# nlp_base_0_2.net
KiCad netlist of a schematic drawn in EasyEDA
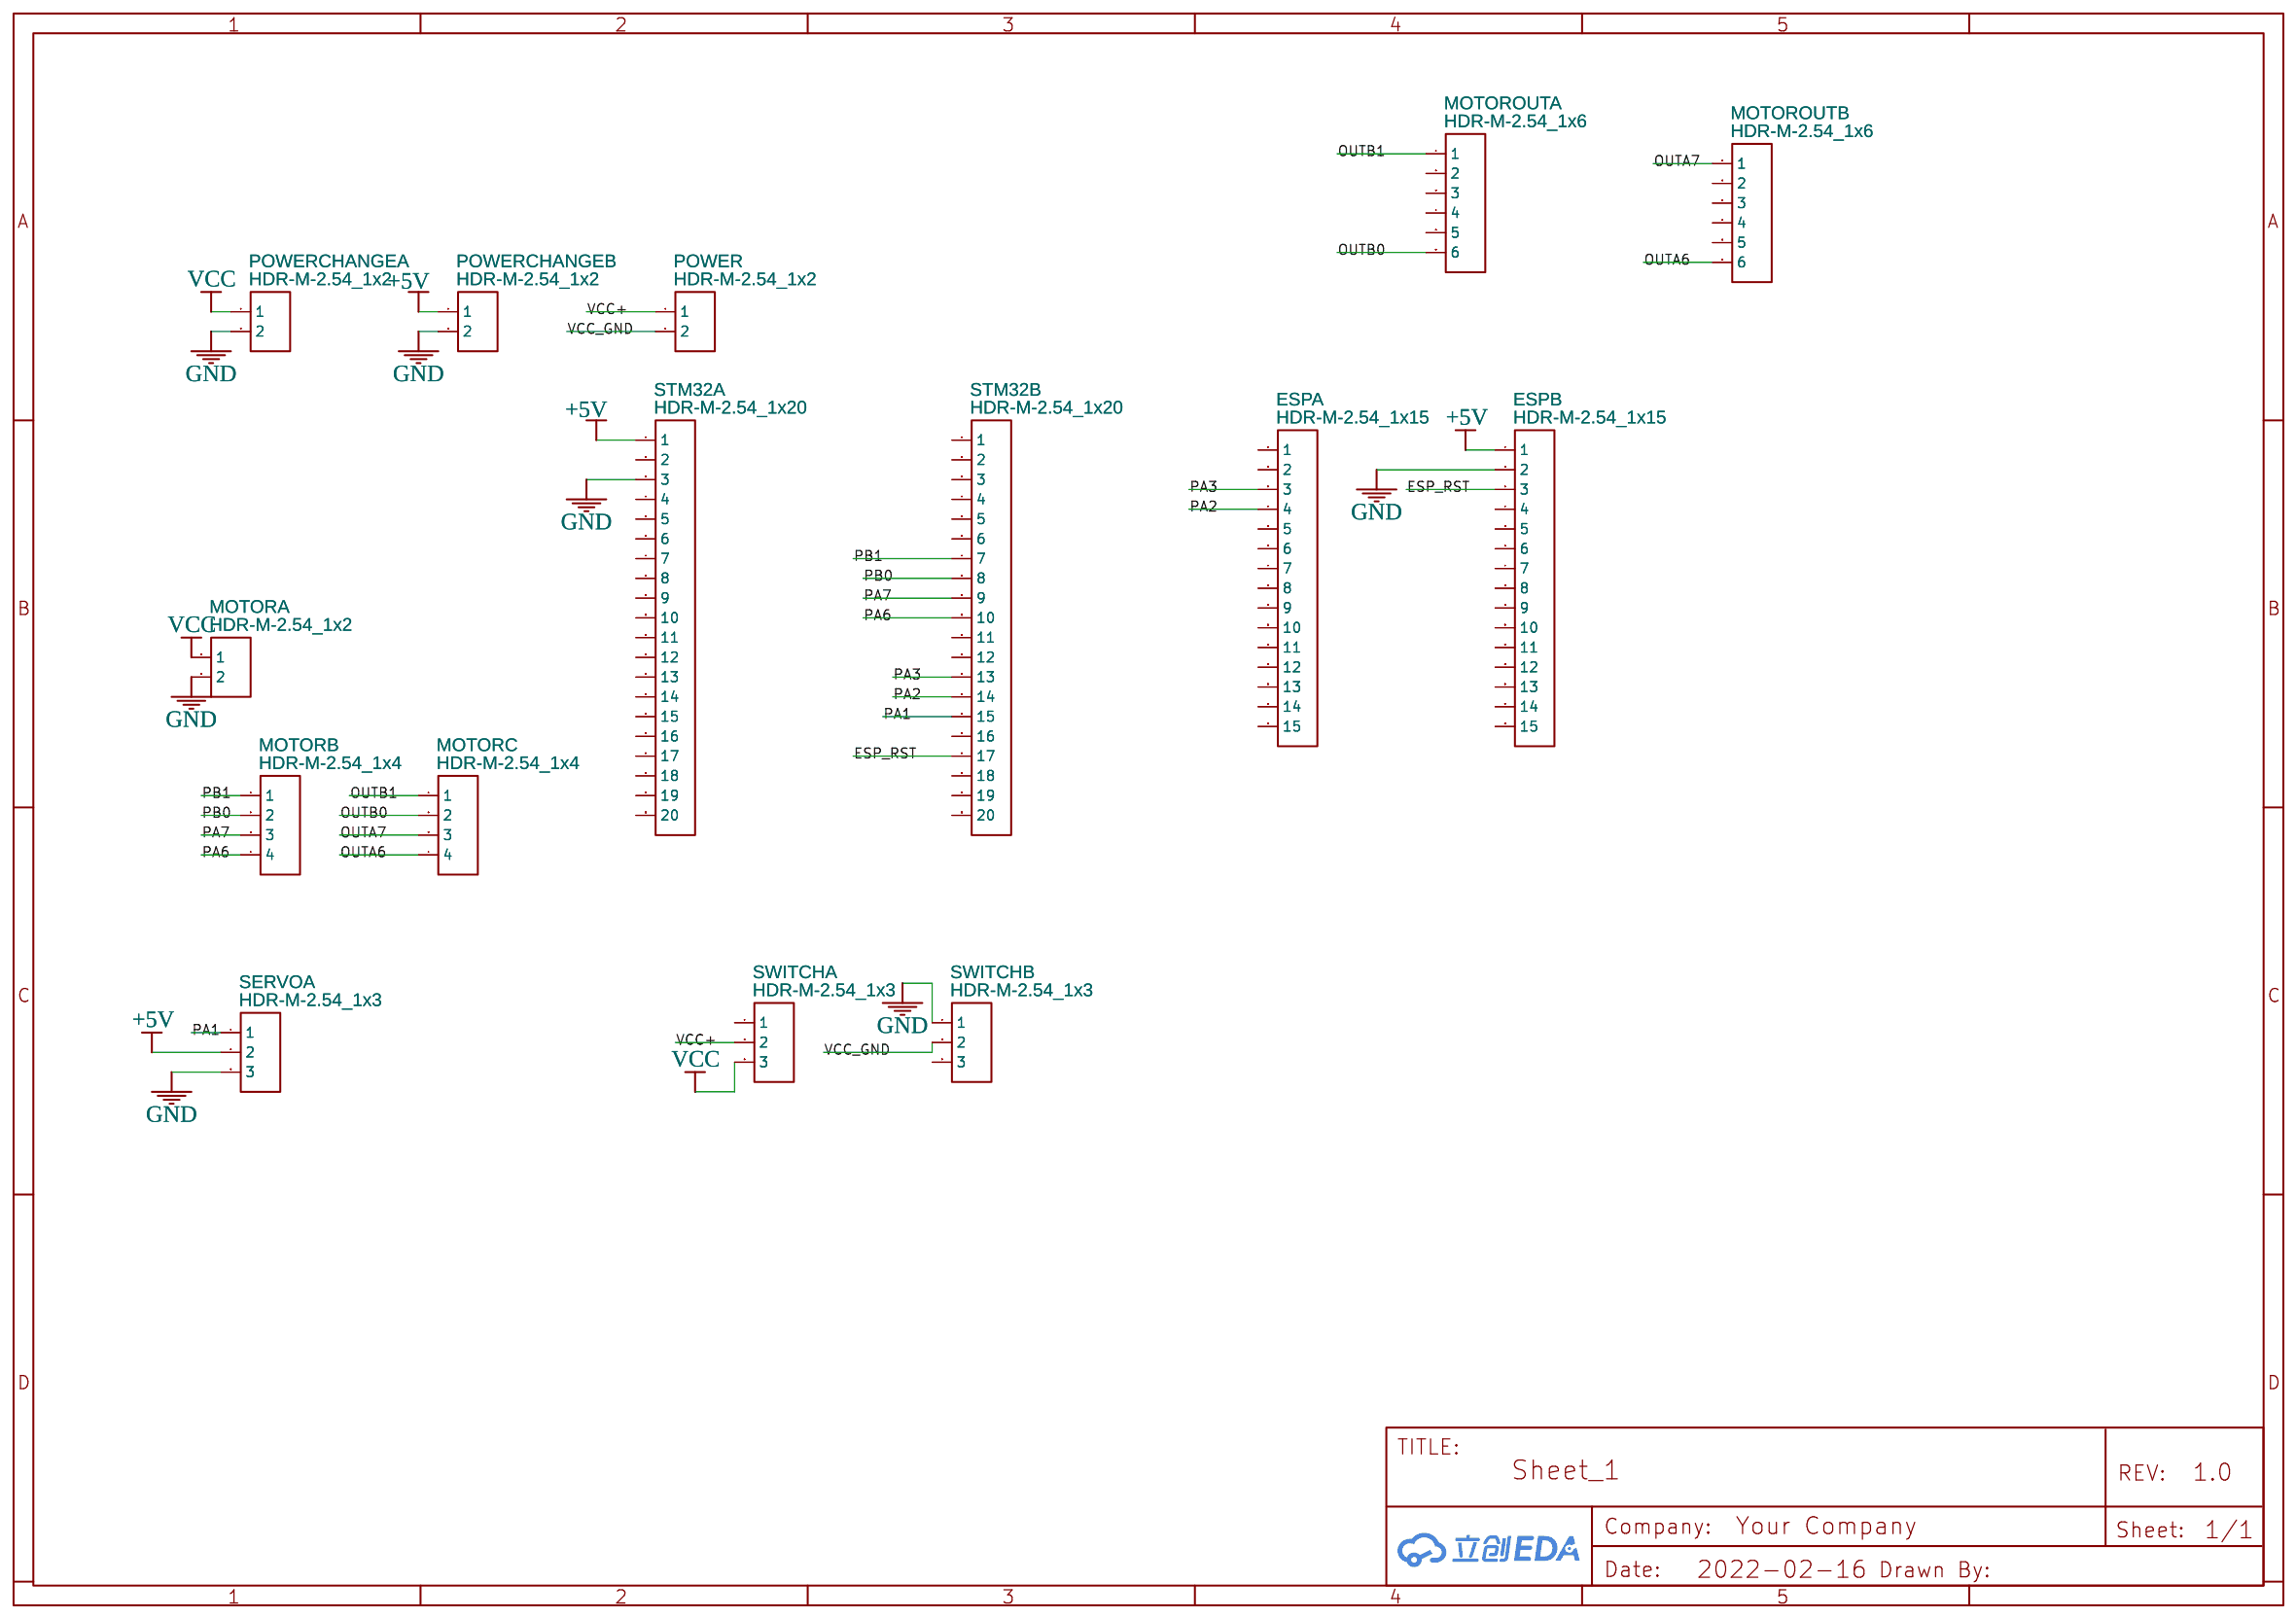
[diagram p0: schematic sheet]

(export (version "E")
  (design (tool "Eeschema 10.0.6"))
  (components
    (comp (ref "ESPA")
      (value "HDR-M-2.54_1x15")
      (fields (field (name "BOM_Supplier Part") "C124373"))
      (libsource (lib "") (part "HDR-M-2.54_1x15_1"))
    )
    (comp (ref "ESPB")
      (value "HDR-M-2.54_1x15")
      (fields (field (name "BOM_Supplier Part") "C124373"))
      (libsource (lib "") (part "HDR-M-2.54_1x15"))
    )
    (comp (ref "MOTORA")
      (value "HDR-M-2.54_1x2")
      (fields (field (name "BOM_Supplier Part") "C124375"))
      (libsource (lib "") (part "HDR-M-2.54_1x2_3"))
    )
    (comp (ref "MOTORB")
      (value "HDR-M-2.54_1x4")
      (fields (field (name "BOM_Supplier Part") "C124378"))
      (libsource (lib "") (part "HDR-M-2.54_1x4_1"))
    )
    (comp (ref "MOTORC")
      (value "HDR-M-2.54_1x4")
      (fields (field (name "BOM_Supplier Part") "C124378"))
      (libsource (lib "") (part "HDR-M-2.54_1x4"))
    )
    (comp (ref "MOTOROUTA")
      (value "HDR-M-2.54_1x6")
      (fields (field (name "BOM_Supplier Part") "C190819"))
      (libsource (lib "") (part "HDR-M-2.54_1x6_1"))
    )
    (comp (ref "MOTOROUTB")
      (value "HDR-M-2.54_1x6")
      (fields (field (name "BOM_Supplier Part") "C190819"))
      (libsource (lib "") (part "HDR-M-2.54_1x6"))
    )
    (comp (ref "POWER")
      (value "HDR-M-2.54_1x2")
      (fields (field (name "BOM_Supplier Part") "C124375"))
      (libsource (lib "") (part "HDR-M-2.54_1x2"))
    )
    (comp (ref "POWERCHANGEA")
      (value "HDR-M-2.54_1x2")
      (fields (field (name "BOM_Supplier Part") "C124375"))
      (libsource (lib "") (part "HDR-M-2.54_1x2_2"))
    )
    (comp (ref "POWERCHANGEB")
      (value "HDR-M-2.54_1x2")
      (fields (field (name "BOM_Supplier Part") "C124375"))
      (libsource (lib "") (part "HDR-M-2.54_1x2_1"))
    )
    (comp (ref "SERVOA")
      (value "HDR-M-2.54_1x3")
      (fields (field (name "BOM_Supplier Part") "C180248"))
      (libsource (lib "") (part "HDR-M-2.54_1x3_2"))
    )
    (comp (ref "STM32A")
      (value "HDR-M-2.54_1x20")
      (fields (field (name "BOM_Supplier Part") "C50981"))
      (libsource (lib "") (part "HDR-M-2.54_1x20_1"))
    )
    (comp (ref "STM32B")
      (value "HDR-M-2.54_1x20")
      (fields (field (name "BOM_Supplier Part") "C50981"))
      (libsource (lib "") (part "HDR-M-2.54_1x20"))
    )
    (comp (ref "SWITCHA")
      (value "HDR-M-2.54_1x3")
      (fields (field (name "BOM_Supplier Part") "C180248"))
      (libsource (lib "") (part "HDR-M-2.54_1x3"))
    )
    (comp (ref "SWITCHB")
      (value "HDR-M-2.54_1x3")
      (fields (field (name "BOM_Supplier Part") "C180248"))
      (libsource (lib "") (part "HDR-M-2.54_1x3_1"))
    )
  )
  (nets
    (net (code "1") (name "+5V") (class "Default")
      (node (ref "ESPB") (pin "1") (pinfunction "1_1") (pintype "unspecified"))
      (node (ref "POWERCHANGEB") (pin "1") (pinfunction "1_1") (pintype "unspecified"))
      (node (ref "SERVOA") (pin "2") (pinfunction "2_2") (pintype "input"))
      (node (ref "STM32A") (pin "1") (pinfunction "1_1") (pintype "unspecified"))
    )
    (net (code "2") (name "/ESP_RST") (class "Default")
      (node (ref "ESPB") (pin "3") (pinfunction "3_3") (pintype "unspecified"))
      (node (ref "STM32B") (pin "17") (pinfunction "17_17") (pintype "unspecified"))
    )
    (net (code "3") (name "/OUTA6") (class "Default")
      (node (ref "MOTORC") (pin "4") (pinfunction "4_4") (pintype "unspecified"))
      (node (ref "MOTOROUTB") (pin "6") (pinfunction "6_6") (pintype "input"))
    )
    (net (code "4") (name "/OUTA7") (class "Default")
      (node (ref "MOTORC") (pin "3") (pinfunction "3_3") (pintype "unspecified"))
      (node (ref "MOTOROUTB") (pin "1") (pinfunction "1_1") (pintype "input"))
    )
    (net (code "5") (name "/OUTB0") (class "Default")
      (node (ref "MOTORC") (pin "2") (pinfunction "2_2") (pintype "unspecified"))
      (node (ref "MOTOROUTA") (pin "6") (pinfunction "6_6") (pintype "input"))
    )
    (net (code "6") (name "/OUTB1") (class "Default")
      (node (ref "MOTORC") (pin "1") (pinfunction "1_1") (pintype "unspecified"))
      (node (ref "MOTOROUTA") (pin "1") (pinfunction "1_1") (pintype "input"))
    )
    (net (code "7") (name "/PA1") (class "Default")
      (node (ref "SERVOA") (pin "1") (pinfunction "1_1") (pintype "input"))
      (node (ref "STM32B") (pin "15") (pinfunction "15_15") (pintype "unspecified"))
    )
    (net (code "8") (name "/PA2") (class "Default")
      (node (ref "ESPA") (pin "4") (pinfunction "4_4") (pintype "unspecified"))
      (node (ref "STM32B") (pin "14") (pinfunction "14_14") (pintype "unspecified"))
    )
    (net (code "9") (name "/PA3") (class "Default")
      (node (ref "ESPA") (pin "3") (pinfunction "3_3") (pintype "unspecified"))
      (node (ref "STM32B") (pin "13") (pinfunction "13_13") (pintype "unspecified"))
    )
    (net (code "10") (name "/PA6") (class "Default")
      (node (ref "MOTORB") (pin "4") (pinfunction "4_4") (pintype "unspecified"))
      (node (ref "STM32B") (pin "10") (pinfunction "10_10") (pintype "unspecified"))
    )
    (net (code "11") (name "/PA7") (class "Default")
      (node (ref "MOTORB") (pin "3") (pinfunction "3_3") (pintype "unspecified"))
      (node (ref "STM32B") (pin "9") (pinfunction "9_9") (pintype "unspecified"))
    )
    (net (code "12") (name "/PB0") (class "Default")
      (node (ref "MOTORB") (pin "2") (pinfunction "2_2") (pintype "unspecified"))
      (node (ref "STM32B") (pin "8") (pinfunction "8_8") (pintype "unspecified"))
    )
    (net (code "13") (name "/PB1") (class "Default")
      (node (ref "MOTORB") (pin "1") (pinfunction "1_1") (pintype "unspecified"))
      (node (ref "STM32B") (pin "7") (pinfunction "7_7") (pintype "unspecified"))
    )
    (net (code "14") (name "/VCC+") (class "Default")
      (node (ref "POWER") (pin "1") (pinfunction "1_1") (pintype "unspecified"))
      (node (ref "SWITCHA") (pin "2") (pinfunction "2_2") (pintype "input"))
    )
    (net (code "15") (name "/VCC_GND") (class "Default")
      (node (ref "POWER") (pin "2") (pinfunction "2_2") (pintype "unspecified"))
      (node (ref "SWITCHB") (pin "2") (pinfunction "2_2") (pintype "input"))
    )
    (net (code "16") (name "GND") (class "Default")
      (node (ref "ESPB") (pin "2") (pinfunction "2_2") (pintype "unspecified"))
      (node (ref "MOTORA") (pin "2") (pinfunction "2_2") (pintype "unspecified"))
      (node (ref "POWERCHANGEA") (pin "2") (pinfunction "2_2") (pintype "unspecified"))
      (node (ref "POWERCHANGEB") (pin "2") (pinfunction "2_2") (pintype "unspecified"))
      (node (ref "SERVOA") (pin "3") (pinfunction "3_3") (pintype "input"))
      (node (ref "STM32A") (pin "3") (pinfunction "3_3") (pintype "unspecified"))
      (node (ref "SWITCHB") (pin "1") (pinfunction "1_1") (pintype "input"))
    )
    (net (code "17") (name "VCC") (class "Default")
      (node (ref "MOTORA") (pin "1") (pinfunction "1_1") (pintype "unspecified"))
      (node (ref "POWERCHANGEA") (pin "1") (pinfunction "1_1") (pintype "unspecified"))
      (node (ref "SWITCHA") (pin "3") (pinfunction "3_3") (pintype "input"))
    )
    (net (code "18") (name "unconnected-(ESPA-Pad1)") (class "Default")
      (node (ref "ESPA") (pin "1") (pinfunction "1_1") (pintype "unspecified"))
    )
    (net (code "19") (name "unconnected-(ESPA-Pad2)") (class "Default")
      (node (ref "ESPA") (pin "2") (pinfunction "2_2") (pintype "unspecified"))
    )
    (net (code "20") (name "unconnected-(ESPA-Pad5)") (class "Default")
      (node (ref "ESPA") (pin "5") (pinfunction "5_5") (pintype "unspecified"))
    )
    (net (code "21") (name "unconnected-(ESPA-Pad6)") (class "Default")
      (node (ref "ESPA") (pin "6") (pinfunction "6_6") (pintype "unspecified"))
    )
    (net (code "22") (name "unconnected-(ESPA-Pad7)") (class "Default")
      (node (ref "ESPA") (pin "7") (pinfunction "7_7") (pintype "unspecified"))
    )
    (net (code "23") (name "unconnected-(ESPA-Pad8)") (class "Default")
      (node (ref "ESPA") (pin "8") (pinfunction "8_8") (pintype "unspecified"))
    )
    (net (code "24") (name "unconnected-(ESPA-Pad9)") (class "Default")
      (node (ref "ESPA") (pin "9") (pinfunction "9_9") (pintype "unspecified"))
    )
    (net (code "25") (name "unconnected-(ESPA-Pad10)") (class "Default")
      (node (ref "ESPA") (pin "10") (pinfunction "10_10") (pintype "unspecified"))
    )
    (net (code "26") (name "unconnected-(ESPA-Pad11)") (class "Default")
      (node (ref "ESPA") (pin "11") (pinfunction "11_11") (pintype "unspecified"))
    )
    (net (code "27") (name "unconnected-(ESPA-Pad12)") (class "Default")
      (node (ref "ESPA") (pin "12") (pinfunction "12_12") (pintype "unspecified"))
    )
    (net (code "28") (name "unconnected-(ESPA-Pad13)") (class "Default")
      (node (ref "ESPA") (pin "13") (pinfunction "13_13") (pintype "unspecified"))
    )
    (net (code "29") (name "unconnected-(ESPA-Pad14)") (class "Default")
      (node (ref "ESPA") (pin "14") (pinfunction "14_14") (pintype "unspecified"))
    )
    (net (code "30") (name "unconnected-(ESPA-Pad15)") (class "Default")
      (node (ref "ESPA") (pin "15") (pinfunction "15_15") (pintype "unspecified"))
    )
    (net (code "31") (name "unconnected-(ESPB-Pad4)") (class "Default")
      (node (ref "ESPB") (pin "4") (pinfunction "4_4") (pintype "unspecified"))
    )
    (net (code "32") (name "unconnected-(ESPB-Pad5)") (class "Default")
      (node (ref "ESPB") (pin "5") (pinfunction "5_5") (pintype "unspecified"))
    )
    (net (code "33") (name "unconnected-(ESPB-Pad6)") (class "Default")
      (node (ref "ESPB") (pin "6") (pinfunction "6_6") (pintype "unspecified"))
    )
    (net (code "34") (name "unconnected-(ESPB-Pad7)") (class "Default")
      (node (ref "ESPB") (pin "7") (pinfunction "7_7") (pintype "unspecified"))
    )
    (net (code "35") (name "unconnected-(ESPB-Pad8)") (class "Default")
      (node (ref "ESPB") (pin "8") (pinfunction "8_8") (pintype "unspecified"))
    )
    (net (code "36") (name "unconnected-(ESPB-Pad9)") (class "Default")
      (node (ref "ESPB") (pin "9") (pinfunction "9_9") (pintype "unspecified"))
    )
    (net (code "37") (name "unconnected-(ESPB-Pad10)") (class "Default")
      (node (ref "ESPB") (pin "10") (pinfunction "10_10") (pintype "unspecified"))
    )
    (net (code "38") (name "unconnected-(ESPB-Pad11)") (class "Default")
      (node (ref "ESPB") (pin "11") (pinfunction "11_11") (pintype "unspecified"))
    )
    (net (code "39") (name "unconnected-(ESPB-Pad12)") (class "Default")
      (node (ref "ESPB") (pin "12") (pinfunction "12_12") (pintype "unspecified"))
    )
    (net (code "40") (name "unconnected-(ESPB-Pad13)") (class "Default")
      (node (ref "ESPB") (pin "13") (pinfunction "13_13") (pintype "unspecified"))
    )
    (net (code "41") (name "unconnected-(ESPB-Pad14)") (class "Default")
      (node (ref "ESPB") (pin "14") (pinfunction "14_14") (pintype "unspecified"))
    )
    (net (code "42") (name "unconnected-(ESPB-Pad15)") (class "Default")
      (node (ref "ESPB") (pin "15") (pinfunction "15_15") (pintype "unspecified"))
    )
    (net (code "43") (name "unconnected-(MOTOROUTA-Pad2)") (class "Default")
      (node (ref "MOTOROUTA") (pin "2") (pinfunction "2_2") (pintype "input"))
    )
    (net (code "44") (name "unconnected-(MOTOROUTA-Pad3)") (class "Default")
      (node (ref "MOTOROUTA") (pin "3") (pinfunction "3_3") (pintype "input"))
    )
    (net (code "45") (name "unconnected-(MOTOROUTA-Pad4)") (class "Default")
      (node (ref "MOTOROUTA") (pin "4") (pinfunction "4_4") (pintype "input"))
    )
    (net (code "46") (name "unconnected-(MOTOROUTA-Pad5)") (class "Default")
      (node (ref "MOTOROUTA") (pin "5") (pinfunction "5_5") (pintype "input"))
    )
    (net (code "47") (name "unconnected-(MOTOROUTB-Pad2)") (class "Default")
      (node (ref "MOTOROUTB") (pin "2") (pinfunction "2_2") (pintype "input"))
    )
    (net (code "48") (name "unconnected-(MOTOROUTB-Pad3)") (class "Default")
      (node (ref "MOTOROUTB") (pin "3") (pinfunction "3_3") (pintype "input"))
    )
    (net (code "49") (name "unconnected-(MOTOROUTB-Pad4)") (class "Default")
      (node (ref "MOTOROUTB") (pin "4") (pinfunction "4_4") (pintype "input"))
    )
    (net (code "50") (name "unconnected-(MOTOROUTB-Pad5)") (class "Default")
      (node (ref "MOTOROUTB") (pin "5") (pinfunction "5_5") (pintype "input"))
    )
    (net (code "51") (name "unconnected-(STM32A-Pad2)") (class "Default")
      (node (ref "STM32A") (pin "2") (pinfunction "2_2") (pintype "unspecified"))
    )
    (net (code "52") (name "unconnected-(STM32A-Pad4)") (class "Default")
      (node (ref "STM32A") (pin "4") (pinfunction "4_4") (pintype "unspecified"))
    )
    (net (code "53") (name "unconnected-(STM32A-Pad5)") (class "Default")
      (node (ref "STM32A") (pin "5") (pinfunction "5_5") (pintype "unspecified"))
    )
    (net (code "54") (name "unconnected-(STM32A-Pad6)") (class "Default")
      (node (ref "STM32A") (pin "6") (pinfunction "6_6") (pintype "unspecified"))
    )
    (net (code "55") (name "unconnected-(STM32A-Pad7)") (class "Default")
      (node (ref "STM32A") (pin "7") (pinfunction "7_7") (pintype "unspecified"))
    )
    (net (code "56") (name "unconnected-(STM32A-Pad8)") (class "Default")
      (node (ref "STM32A") (pin "8") (pinfunction "8_8") (pintype "unspecified"))
    )
    (net (code "57") (name "unconnected-(STM32A-Pad9)") (class "Default")
      (node (ref "STM32A") (pin "9") (pinfunction "9_9") (pintype "unspecified"))
    )
    (net (code "58") (name "unconnected-(STM32A-Pad10)") (class "Default")
      (node (ref "STM32A") (pin "10") (pinfunction "10_10") (pintype "unspecified"))
    )
    (net (code "59") (name "unconnected-(STM32A-Pad11)") (class "Default")
      (node (ref "STM32A") (pin "11") (pinfunction "11_11") (pintype "unspecified"))
    )
    (net (code "60") (name "unconnected-(STM32A-Pad12)") (class "Default")
      (node (ref "STM32A") (pin "12") (pinfunction "12_12") (pintype "unspecified"))
    )
    (net (code "61") (name "unconnected-(STM32A-Pad13)") (class "Default")
      (node (ref "STM32A") (pin "13") (pinfunction "13_13") (pintype "unspecified"))
    )
    (net (code "62") (name "unconnected-(STM32A-Pad14)") (class "Default")
      (node (ref "STM32A") (pin "14") (pinfunction "14_14") (pintype "unspecified"))
    )
    (net (code "63") (name "unconnected-(STM32A-Pad15)") (class "Default")
      (node (ref "STM32A") (pin "15") (pinfunction "15_15") (pintype "unspecified"))
    )
    (net (code "64") (name "unconnected-(STM32A-Pad16)") (class "Default")
      (node (ref "STM32A") (pin "16") (pinfunction "16_16") (pintype "unspecified"))
    )
    (net (code "65") (name "unconnected-(STM32A-Pad17)") (class "Default")
      (node (ref "STM32A") (pin "17") (pinfunction "17_17") (pintype "unspecified"))
    )
    (net (code "66") (name "unconnected-(STM32A-Pad18)") (class "Default")
      (node (ref "STM32A") (pin "18") (pinfunction "18_18") (pintype "unspecified"))
    )
    (net (code "67") (name "unconnected-(STM32A-Pad19)") (class "Default")
      (node (ref "STM32A") (pin "19") (pinfunction "19_19") (pintype "unspecified"))
    )
    (net (code "68") (name "unconnected-(STM32A-Pad20)") (class "Default")
      (node (ref "STM32A") (pin "20") (pinfunction "20_20") (pintype "unspecified"))
    )
    (net (code "69") (name "unconnected-(STM32B-Pad1)") (class "Default")
      (node (ref "STM32B") (pin "1") (pinfunction "1_1") (pintype "unspecified"))
    )
    (net (code "70") (name "unconnected-(STM32B-Pad2)") (class "Default")
      (node (ref "STM32B") (pin "2") (pinfunction "2_2") (pintype "unspecified"))
    )
    (net (code "71") (name "unconnected-(STM32B-Pad3)") (class "Default")
      (node (ref "STM32B") (pin "3") (pinfunction "3_3") (pintype "unspecified"))
    )
    (net (code "72") (name "unconnected-(STM32B-Pad4)") (class "Default")
      (node (ref "STM32B") (pin "4") (pinfunction "4_4") (pintype "unspecified"))
    )
    (net (code "73") (name "unconnected-(STM32B-Pad5)") (class "Default")
      (node (ref "STM32B") (pin "5") (pinfunction "5_5") (pintype "unspecified"))
    )
    (net (code "74") (name "unconnected-(STM32B-Pad6)") (class "Default")
      (node (ref "STM32B") (pin "6") (pinfunction "6_6") (pintype "unspecified"))
    )
    (net (code "75") (name "unconnected-(STM32B-Pad11)") (class "Default")
      (node (ref "STM32B") (pin "11") (pinfunction "11_11") (pintype "unspecified"))
    )
    (net (code "76") (name "unconnected-(STM32B-Pad12)") (class "Default")
      (node (ref "STM32B") (pin "12") (pinfunction "12_12") (pintype "unspecified"))
    )
    (net (code "77") (name "unconnected-(STM32B-Pad16)") (class "Default")
      (node (ref "STM32B") (pin "16") (pinfunction "16_16") (pintype "unspecified"))
    )
    (net (code "78") (name "unconnected-(STM32B-Pad18)") (class "Default")
      (node (ref "STM32B") (pin "18") (pinfunction "18_18") (pintype "unspecified"))
    )
    (net (code "79") (name "unconnected-(STM32B-Pad19)") (class "Default")
      (node (ref "STM32B") (pin "19") (pinfunction "19_19") (pintype "unspecified"))
    )
    (net (code "80") (name "unconnected-(STM32B-Pad20)") (class "Default")
      (node (ref "STM32B") (pin "20") (pinfunction "20_20") (pintype "unspecified"))
    )
    (net (code "81") (name "unconnected-(SWITCHA-Pad1)") (class "Default")
      (node (ref "SWITCHA") (pin "1") (pinfunction "1_1") (pintype "input"))
    )
    (net (code "82") (name "unconnected-(SWITCHB-Pad3)") (class "Default")
      (node (ref "SWITCHB") (pin "3") (pinfunction "3_3") (pintype "input"))
    )
  )
)
